# cs301_YourGroupNumber.net
KiCad netlist of a schematic drawn in Altium Designer
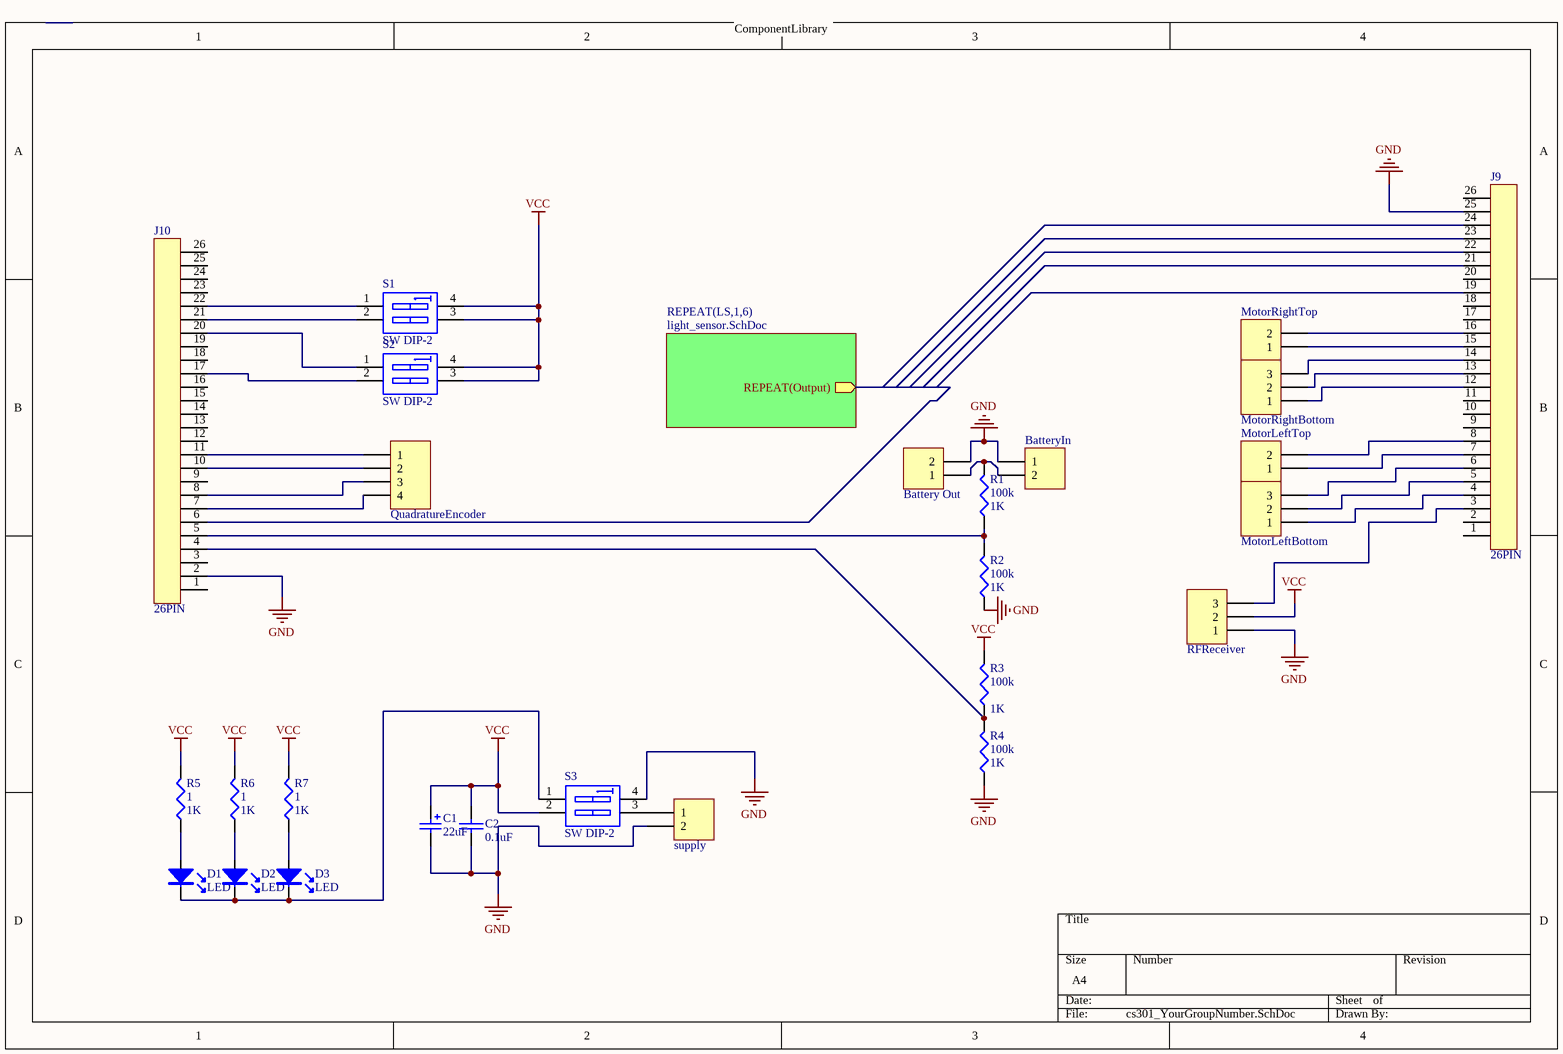
[diagram p0: cs301_YourGroupNumber.SchDoc]

(export (version "E")
  (design (tool "Eeschema 10.0.6"))
  (components
    (comp (ref "Battery Out")
      (value "2 Way")
      (footprint "ECE-600102STTH")
      (description "HEADER POLARISED 2WAY TH")
      (libsource (lib "EceParts") (part "Header 2"))
    )
    (comp (ref "BatteryIn")
      (value "2 Way")
      (footprint "ECE-600102STTH")
      (description "HEADER POLARISED 2WAY TH")
      (libsource (lib "") (part "Header 2_1"))
    )
    (comp (ref "C1")
      (value "22uF")
      (footprint "ECE-CAPAE6.3X5.4SM")
      (description "Polarized Capacitor (Radial)")
      (libsource (lib "EE209-SMT") (part "CAP 22uF/35V SM"))
    )
    (comp (ref "C2")
      (value "0.1uF")
      (footprint "ECE-CAPC2012-0805SM")
      (description "Capacitor")
      (libsource (lib "EE209-SMT") (part "CAP 0805 SM"))
    )
    (comp (ref "D1") (value "LED") (footprint "LED0.1/5MM") (libsource (lib "COMSYS301_2013") (part "LED")))
    (comp (ref "D2") (value "LED") (footprint "LED0.1/5MM") (libsource (lib "COMSYS301_2013") (part "LED")))
    (comp (ref "D3") (value "LED") (footprint "LED0.1/5MM") (libsource (lib "COMSYS301_2013") (part "LED")))
    (comp (ref "J9") (value "26PIN") (footprint "SIP26") (libsource (lib "") (part "26PIN_1")))
    (comp (ref "J10")
      (value "26PIN")
      (footprint "SIP26")
      (libsource (lib "Miscellaneous Devices") (part "26PIN"))
    )
    (comp (ref "MotorLeftBottom")
      (value "3 Way")
      (footprint "ECE-600103STTH")
      (description "HEADER POLARISED 3WAY TH")
      (libsource (lib "EceParts") (part "Header 3"))
    )
    (comp (ref "MotorLeftTop")
      (value "2 Way")
      (footprint "ECE-600102STTH")
      (description "HEADER POLARISED 2WAY TH")
      (libsource (lib "EceParts") (part "Header 2"))
    )
    (comp (ref "MotorRightBottom")
      (value "3 Way")
      (footprint "ECE-600103STTH")
      (description "HEADER POLARISED 3WAY TH")
      (libsource (lib "EceParts") (part "Header 3"))
    )
    (comp (ref "MotorRightTop")
      (value "2 Way")
      (footprint "ECE-600102STTH")
      (description "HEADER POLARISED 2WAY TH")
      (libsource (lib "EceParts") (part "Header 2"))
    )
    (comp (ref "QuadratureEncoder")
      (value "4 Way")
      (footprint "ECE-600104STTH")
      (description "HEADER POLARISED 4WAY TH")
      (libsource (lib "EceParts") (part "Header 4"))
    )
    (comp (ref "R1")
      (value "100k")
      (footprint "J1-0603")
      (description "Resistor")
      (fields (field (name "ALTIUM_VALUE") "1K") (field (name "PUBLISHER") "Altium Limited"))
      (libsource (lib "Miscellaneous Devices") (part "Res3"))
    )
    (comp (ref "R2")
      (value "100k")
      (footprint "J1-0603")
      (description "Resistor")
      (fields (field (name "ALTIUM_VALUE") "1K") (field (name "PUBLISHER") "Altium Limited"))
      (libsource (lib "Miscellaneous Devices") (part "Res3"))
    )
    (comp (ref "R3")
      (value "100k")
      (footprint "J1-0603")
      (description "Resistor")
      (fields (field (name "ALTIUM_VALUE") "1K") (field (name "PUBLISHER") "Altium Limited"))
      (libsource (lib "Miscellaneous Devices") (part "Res3"))
    )
    (comp (ref "R4")
      (value "100k")
      (footprint "J1-0603")
      (description "Resistor")
      (fields (field (name "ALTIUM_VALUE") "1K") (field (name "PUBLISHER") "Altium Limited"))
      (libsource (lib "Miscellaneous Devices") (part "Res3"))
    )
    (comp (ref "R5")
      (value "1")
      (footprint "J1-0603")
      (description "Resistor")
      (fields (field (name "ALTIUM_VALUE") "1K") (field (name "PUBLISHER") "Altium Limited"))
      (libsource (lib "Miscellaneous Devices") (part "Res3"))
    )
    (comp (ref "R6")
      (value "1")
      (footprint "J1-0603")
      (description "Resistor")
      (fields (field (name "ALTIUM_VALUE") "1K") (field (name "PUBLISHER") "Altium Limited"))
      (libsource (lib "Miscellaneous Devices") (part "Res3"))
    )
    (comp (ref "R7")
      (value "1")
      (footprint "J1-0603")
      (description "Resistor")
      (fields (field (name "ALTIUM_VALUE") "1K") (field (name "PUBLISHER") "Altium Limited"))
      (libsource (lib "Miscellaneous Devices") (part "Res3"))
    )
    (comp (ref "RFReceiver")
      (value "3 Way")
      (footprint "ECE-600103STTH")
      (description "HEADER POLARISED 3WAY TH")
      (libsource (lib "EceParts") (part "Header 3"))
    )
    (comp (ref "S1")
      (value "SW DIP-2")
      (footprint "DIP-4")
      (description "DIP Switch, 2 Position, SPST")
      (fields (field (name "PUBLISHER") "Altium Limited"))
      (libsource (lib "Miscellaneous Devices") (part "SW DIP-2"))
    )
    (comp (ref "S2")
      (value "SW DIP-2")
      (footprint "DIP-4")
      (description "DIP Switch, 2 Position, SPST")
      (fields (field (name "PUBLISHER") "Altium Limited"))
      (libsource (lib "Miscellaneous Devices") (part "SW DIP-2"))
    )
    (comp (ref "S3")
      (value "SW DIP-2")
      (footprint "DIP-4")
      (description "DIP Switch, 2 Position, SPST")
      (fields (field (name "PUBLISHER") "Altium Limited"))
      (libsource (lib "Miscellaneous Devices") (part "SW DIP-2"))
    )
    (comp (ref "supply")
      (value "2 Way")
      (footprint "ECE-600102STTH")
      (description "HEADER POLARISED 2WAY TH")
      (libsource (lib "") (part "Header 2_1"))
    )
  )
  (nets
    (net (code "2") (name "GND") (class "Default")
      (node (ref "Battery Out") (pin "2") (pinfunction "2_2") (pintype "passive"))
      (node (ref "BatteryIn") (pin "1") (pinfunction "1_1") (pintype "passive"))
      (node (ref "C1") (pin "2") (pinfunction "2_2") (pintype "passive"))
      (node (ref "C2") (pin "2") (pinfunction "2_2") (pintype "passive"))
      (node (ref "J10") (pin "2") (pinfunction "2_2") (pintype "passive"))
      (node (ref "J9") (pin "25") (pinfunction "25_25") (pintype "passive"))
      (node (ref "R2") (pin "1") (pinfunction "1_1") (pintype "passive"))
      (node (ref "R4") (pin "1") (pinfunction "1_1") (pintype "passive"))
      (node (ref "RFReceiver") (pin "1") (pinfunction "1_1") (pintype "passive"))
      (node (ref "S3") (pin "4") (pinfunction "B1_4") (pintype "passive"))
      (node (ref "supply") (pin "2") (pinfunction "2_2") (pintype "passive"))
    )
    (net (code "3") (name "Net-(Battery Out-Pad1)") (class "Default")
      (node (ref "Battery Out") (pin "1") (pinfunction "1_1") (pintype "passive"))
      (node (ref "BatteryIn") (pin "2") (pinfunction "2_2") (pintype "passive"))
      (node (ref "R1") (pin "2") (pinfunction "2_2") (pintype "passive"))
    )
    (net (code "4") (name "Net-(D1-1)") (class "Default")
      (node (ref "D1") (pin "A") (pinfunction "1_A") (pintype "passive"))
      (node (ref "R5") (pin "1") (pinfunction "1_1") (pintype "passive"))
    )
    (net (code "5") (name "Net-(D1-2)") (class "Default")
      (node (ref "D1") (pin "K") (pinfunction "2_K") (pintype "passive"))
      (node (ref "D2") (pin "K") (pinfunction "2_K") (pintype "passive"))
      (node (ref "D3") (pin "K") (pinfunction "2_K") (pintype "passive"))
      (node (ref "S3") (pin "1") (pinfunction "A1_1") (pintype "passive"))
    )
    (net (code "6") (name "Net-(D2-1)") (class "Default")
      (node (ref "D2") (pin "A") (pinfunction "1_A") (pintype "passive"))
      (node (ref "R6") (pin "1") (pinfunction "1_1") (pintype "passive"))
    )
    (net (code "7") (name "Net-(D3-1)") (class "Default")
      (node (ref "D3") (pin "A") (pinfunction "1_A") (pintype "passive"))
      (node (ref "R7") (pin "1") (pinfunction "1_1") (pintype "passive"))
    )
    (net (code "8") (name "Net-(J9-Pad3)") (class "Default")
      (node (ref "J9") (pin "3") (pinfunction "3_3") (pintype "passive"))
      (node (ref "RFReceiver") (pin "3") (pinfunction "3_3") (pintype "passive"))
    )
    (net (code "9") (name "Net-(J9-Pad4)") (class "Default")
      (node (ref "J9") (pin "4") (pinfunction "4_4") (pintype "passive"))
      (node (ref "MotorLeftBottom") (pin "1") (pinfunction "1_1") (pintype "passive"))
    )
    (net (code "10") (name "Net-(J9-Pad5)") (class "Default")
      (node (ref "J9") (pin "5") (pinfunction "5_5") (pintype "passive"))
      (node (ref "MotorLeftBottom") (pin "2") (pinfunction "2_2") (pintype "passive"))
    )
    (net (code "11") (name "Net-(J9-Pad6)") (class "Default")
      (node (ref "J9") (pin "6") (pinfunction "6_6") (pintype "passive"))
      (node (ref "MotorLeftBottom") (pin "3") (pinfunction "3_3") (pintype "passive"))
    )
    (net (code "12") (name "Net-(J9-Pad7)") (class "Default")
      (node (ref "J9") (pin "7") (pinfunction "7_7") (pintype "passive"))
      (node (ref "MotorLeftTop") (pin "1") (pinfunction "1_1") (pintype "passive"))
    )
    (net (code "13") (name "Net-(J9-Pad8)") (class "Default")
      (node (ref "J9") (pin "8") (pinfunction "8_8") (pintype "passive"))
      (node (ref "MotorLeftTop") (pin "2") (pinfunction "2_2") (pintype "passive"))
    )
    (net (code "14") (name "Net-(J9-Pad12)") (class "Default")
      (node (ref "J9") (pin "12") (pinfunction "12_12") (pintype "passive"))
      (node (ref "MotorRightBottom") (pin "1") (pinfunction "1_1") (pintype "passive"))
    )
    (net (code "15") (name "Net-(J9-Pad13)") (class "Default")
      (node (ref "J9") (pin "13") (pinfunction "13_13") (pintype "passive"))
      (node (ref "MotorRightBottom") (pin "2") (pinfunction "2_2") (pintype "passive"))
    )
    (net (code "16") (name "Net-(J9-Pad14)") (class "Default")
      (node (ref "J9") (pin "14") (pinfunction "14_14") (pintype "passive"))
      (node (ref "MotorRightBottom") (pin "3") (pinfunction "3_3") (pintype "passive"))
    )
    (net (code "17") (name "Net-(J9-Pad15)") (class "Default")
      (node (ref "J9") (pin "15") (pinfunction "15_15") (pintype "passive"))
      (node (ref "MotorRightTop") (pin "1") (pinfunction "1_1") (pintype "passive"))
    )
    (net (code "18") (name "Net-(J9-Pad16)") (class "Default")
      (node (ref "J9") (pin "16") (pinfunction "16_16") (pintype "passive"))
      (node (ref "MotorRightTop") (pin "2") (pinfunction "2_2") (pintype "passive"))
    )
    (net (code "19") (name "Net-(J10-Pad4)") (class "Default")
      (node (ref "J10") (pin "4") (pinfunction "4_4") (pintype "passive"))
      (node (ref "R3") (pin "1") (pinfunction "1_1") (pintype "passive"))
      (node (ref "R4") (pin "2") (pinfunction "2_2") (pintype "passive"))
    )
    (net (code "20") (name "Net-(J10-Pad5)") (class "Default")
      (node (ref "J10") (pin "5") (pinfunction "5_5") (pintype "passive"))
      (node (ref "R1") (pin "1") (pinfunction "1_1") (pintype "passive"))
      (node (ref "R2") (pin "2") (pinfunction "2_2") (pintype "passive"))
    )
    (net (code "21") (name "Net-(J10-Pad7)") (class "Default")
      (node (ref "J10") (pin "7") (pinfunction "7_7") (pintype "passive"))
      (node (ref "QuadratureEncoder") (pin "4") (pinfunction "4_4") (pintype "passive"))
    )
    (net (code "22") (name "Net-(J10-Pad8)") (class "Default")
      (node (ref "J10") (pin "8") (pinfunction "8_8") (pintype "passive"))
      (node (ref "QuadratureEncoder") (pin "3") (pinfunction "3_3") (pintype "passive"))
    )
    (net (code "23") (name "Net-(J10-Pad10)") (class "Default")
      (node (ref "J10") (pin "10") (pinfunction "10_10") (pintype "passive"))
      (node (ref "QuadratureEncoder") (pin "2") (pinfunction "2_2") (pintype "passive"))
    )
    (net (code "24") (name "Net-(J10-Pad11)") (class "Default")
      (node (ref "J10") (pin "11") (pinfunction "11_11") (pintype "passive"))
      (node (ref "QuadratureEncoder") (pin "1") (pinfunction "1_1") (pintype "passive"))
    )
    (net (code "25") (name "Net-(S1-A1)") (class "Default")
      (node (ref "J10") (pin "22") (pinfunction "22_22") (pintype "passive"))
      (node (ref "S1") (pin "1") (pinfunction "A1_1") (pintype "passive"))
    )
    (net (code "26") (name "Net-(S1-A2)") (class "Default")
      (node (ref "J10") (pin "21") (pinfunction "21_21") (pintype "passive"))
      (node (ref "S1") (pin "2") (pinfunction "A2_2") (pintype "passive"))
    )
    (net (code "27") (name "Net-(S2-A1)") (class "Default")
      (node (ref "J10") (pin "20") (pinfunction "20_20") (pintype "passive"))
      (node (ref "S2") (pin "1") (pinfunction "A1_1") (pintype "passive"))
    )
    (net (code "28") (name "Net-(S2-A2)") (class "Default")
      (node (ref "J10") (pin "17") (pinfunction "17_17") (pintype "passive"))
      (node (ref "S2") (pin "2") (pinfunction "A2_2") (pintype "passive"))
    )
    (net (code "29") (name "Net-(S3-B2)") (class "Default")
      (node (ref "S3") (pin "3") (pinfunction "B2_3") (pintype "passive"))
      (node (ref "supply") (pin "1") (pinfunction "1_1") (pintype "passive"))
    )
    (net (code "30") (name "VCC") (class "Default")
      (node (ref "C1") (pin "1") (pinfunction "1_1") (pintype "passive"))
      (node (ref "C2") (pin "1") (pinfunction "1_1") (pintype "passive"))
      (node (ref "R3") (pin "2") (pinfunction "2_2") (pintype "passive"))
      (node (ref "R5") (pin "2") (pinfunction "2_2") (pintype "passive"))
      (node (ref "R6") (pin "2") (pinfunction "2_2") (pintype "passive"))
      (node (ref "R7") (pin "2") (pinfunction "2_2") (pintype "passive"))
      (node (ref "RFReceiver") (pin "2") (pinfunction "2_2") (pintype "passive"))
      (node (ref "S1") (pin "3") (pinfunction "B2_3") (pintype "passive"))
      (node (ref "S1") (pin "4") (pinfunction "B1_4") (pintype "passive"))
      (node (ref "S2") (pin "3") (pinfunction "B2_3") (pintype "passive"))
      (node (ref "S2") (pin "4") (pinfunction "B1_4") (pintype "passive"))
      (node (ref "S3") (pin "2") (pinfunction "A2_2") (pintype "passive"))
    )
    (net (code "31") (name "unconnected-(J9-Pad1)") (class "Default")
      (node (ref "J9") (pin "1") (pinfunction "1_1") (pintype "passive"))
    )
    (net (code "32") (name "unconnected-(J9-Pad2)") (class "Default")
      (node (ref "J9") (pin "2") (pinfunction "2_2") (pintype "passive"))
    )
    (net (code "33") (name "unconnected-(J9-Pad9)") (class "Default")
      (node (ref "J9") (pin "9") (pinfunction "9_9") (pintype "passive"))
    )
    (net (code "34") (name "unconnected-(J9-Pad10)") (class "Default")
      (node (ref "J9") (pin "10") (pinfunction "10_10") (pintype "passive"))
    )
    (net (code "35") (name "unconnected-(J9-Pad11)") (class "Default")
      (node (ref "J9") (pin "11") (pinfunction "11_11") (pintype "passive"))
    )
    (net (code "36") (name "unconnected-(J9-Pad17)") (class "Default")
      (node (ref "J9") (pin "17") (pinfunction "17_17") (pintype "passive"))
    )
    (net (code "37") (name "unconnected-(J9-Pad18)") (class "Default")
      (node (ref "J9") (pin "18") (pinfunction "18_18") (pintype "passive"))
    )
    (net (code "38") (name "unconnected-(J9-Pad19)") (class "Default")
      (node (ref "J9") (pin "19") (pinfunction "19_19") (pintype "passive"))
    )
    (net (code "39") (name "unconnected-(J9-Pad20)") (class "Default")
      (node (ref "J9") (pin "20") (pinfunction "20_20") (pintype "passive"))
    )
    (net (code "40") (name "unconnected-(J9-Pad21)") (class "Default")
      (node (ref "J9") (pin "21") (pinfunction "21_21") (pintype "passive"))
    )
    (net (code "41") (name "unconnected-(J9-Pad22)") (class "Default")
      (node (ref "J9") (pin "22") (pinfunction "22_22") (pintype "passive"))
    )
    (net (code "42") (name "unconnected-(J9-Pad23)") (class "Default")
      (node (ref "J9") (pin "23") (pinfunction "23_23") (pintype "passive"))
    )
    (net (code "43") (name "unconnected-(J9-Pad24)") (class "Default")
      (node (ref "J9") (pin "24") (pinfunction "24_24") (pintype "passive"))
    )
    (net (code "44") (name "unconnected-(J9-Pad26)") (class "Default")
      (node (ref "J9") (pin "26") (pinfunction "26_26") (pintype "passive"))
    )
    (net (code "45") (name "unconnected-(J10-Pad1)") (class "Default")
      (node (ref "J10") (pin "1") (pinfunction "1_1") (pintype "passive"))
    )
    (net (code "46") (name "unconnected-(J10-Pad3)") (class "Default")
      (node (ref "J10") (pin "3") (pinfunction "3_3") (pintype "passive"))
    )
    (net (code "47") (name "unconnected-(J10-Pad6)") (class "Default")
      (node (ref "J10") (pin "6") (pinfunction "6_6") (pintype "passive"))
    )
    (net (code "48") (name "unconnected-(J10-Pad9)") (class "Default")
      (node (ref "J10") (pin "9") (pinfunction "9_9") (pintype "passive"))
    )
    (net (code "49") (name "unconnected-(J10-Pad12)") (class "Default")
      (node (ref "J10") (pin "12") (pinfunction "12_12") (pintype "passive"))
    )
    (net (code "50") (name "unconnected-(J10-Pad13)") (class "Default")
      (node (ref "J10") (pin "13") (pinfunction "13_13") (pintype "passive"))
    )
    (net (code "51") (name "unconnected-(J10-Pad14)") (class "Default")
      (node (ref "J10") (pin "14") (pinfunction "14_14") (pintype "passive"))
    )
    (net (code "52") (name "unconnected-(J10-Pad15)") (class "Default")
      (node (ref "J10") (pin "15") (pinfunction "15_15") (pintype "passive"))
    )
    (net (code "53") (name "unconnected-(J10-Pad16)") (class "Default")
      (node (ref "J10") (pin "16") (pinfunction "16_16") (pintype "passive"))
    )
    (net (code "54") (name "unconnected-(J10-Pad18)") (class "Default")
      (node (ref "J10") (pin "18") (pinfunction "18_18") (pintype "passive"))
    )
    (net (code "55") (name "unconnected-(J10-Pad19)") (class "Default")
      (node (ref "J10") (pin "19") (pinfunction "19_19") (pintype "passive"))
    )
    (net (code "56") (name "unconnected-(J10-Pad23)") (class "Default")
      (node (ref "J10") (pin "23") (pinfunction "23_23") (pintype "passive"))
    )
    (net (code "57") (name "unconnected-(J10-Pad24)") (class "Default")
      (node (ref "J10") (pin "24") (pinfunction "24_24") (pintype "passive"))
    )
    (net (code "58") (name "unconnected-(J10-Pad25)") (class "Default")
      (node (ref "J10") (pin "25") (pinfunction "25_25") (pintype "passive"))
    )
    (net (code "59") (name "unconnected-(J10-Pad26)") (class "Default")
      (node (ref "J10") (pin "26") (pinfunction "26_26") (pintype "passive"))
    )
  )
)
